# Topshell_V1_2.net
KiCad netlist of a schematic drawn in EAGLE
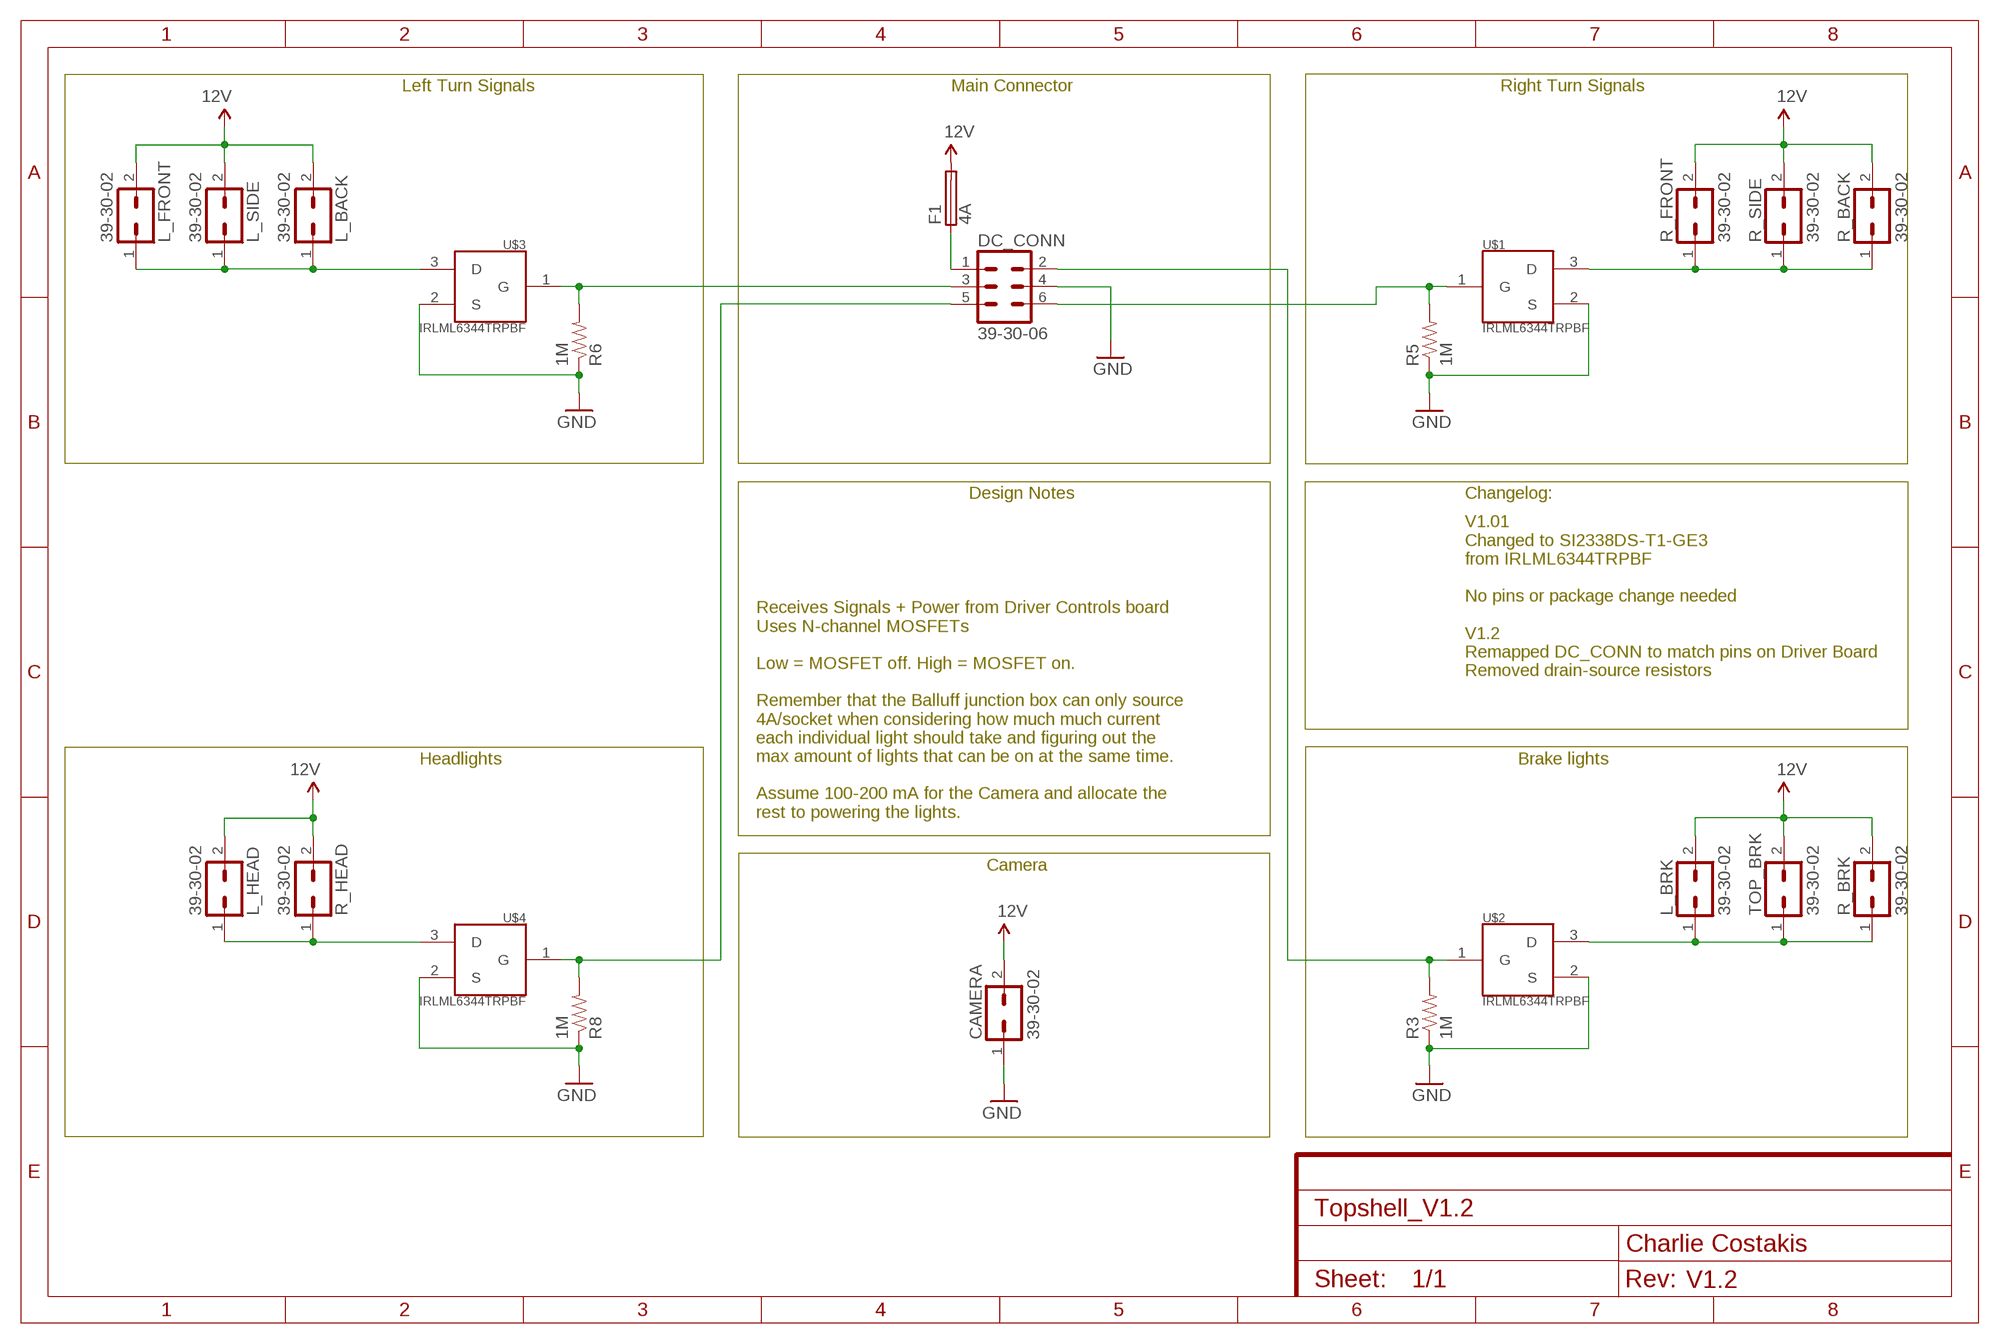
[diagram p0: schematic, sheet 1]

(export (version "E")
  (design (tool "Eeschema 10.0.6"))
  (components
    (comp (ref "CAMERA")
      (value "39-30-02")
      (footprint "eagle-import:39-30-_02_")
      (libsource (lib "eagle-import") (part "39-30-?02?"))
    )
    (comp (ref "DC_CONN")
      (value "39-30-06")
      (footprint "eagle-import:39-30-_06_")
      (libsource (lib "eagle-import") (part "39-30-?06?"))
    )
    (comp (ref "F1")
      (value "4A")
      (footprint "eagle-import:OMNIBLOK")
      (libsource (lib "eagle-import") (part "SMD-MICRO-FUSE-BLOCK"))
    )
    (comp (ref "L_BACK")
      (value "39-30-02")
      (footprint "eagle-import:39-30-_02_")
      (libsource (lib "eagle-import") (part "39-30-?02?"))
    )
    (comp (ref "L_BRK")
      (value "39-30-02")
      (footprint "eagle-import:39-30-_02_")
      (libsource (lib "eagle-import") (part "39-30-?02?"))
    )
    (comp (ref "L_FRONT")
      (value "39-30-02")
      (footprint "eagle-import:39-30-_02_")
      (libsource (lib "eagle-import") (part "39-30-?02?"))
    )
    (comp (ref "L_HEAD")
      (value "39-30-02")
      (footprint "eagle-import:39-30-_02_")
      (libsource (lib "eagle-import") (part "39-30-?02?"))
    )
    (comp (ref "L_SIDE")
      (value "39-30-02")
      (footprint "eagle-import:39-30-_02_")
      (libsource (lib "eagle-import") (part "39-30-?02?"))
    )
    (comp (ref "R3")
      (value "1M")
      (footprint "eagle-import:0805")
      (libsource (lib "eagle-import") (part "RESISTOR0805-RES"))
    )
    (comp (ref "R5")
      (value "1M")
      (footprint "eagle-import:0805")
      (libsource (lib "eagle-import") (part "RESISTOR0805-RES"))
    )
    (comp (ref "R6")
      (value "1M")
      (footprint "eagle-import:0805")
      (libsource (lib "eagle-import") (part "RESISTOR0805-RES"))
    )
    (comp (ref "R8")
      (value "1M")
      (footprint "eagle-import:0805")
      (libsource (lib "eagle-import") (part "RESISTOR0805-RES"))
    )
    (comp (ref "R_BACK")
      (value "39-30-02")
      (footprint "eagle-import:39-30-_02_")
      (libsource (lib "eagle-import") (part "39-30-?02?"))
    )
    (comp (ref "R_BRK")
      (value "39-30-02")
      (footprint "eagle-import:39-30-_02_")
      (libsource (lib "eagle-import") (part "39-30-?02?"))
    )
    (comp (ref "R_FRONT")
      (value "39-30-02")
      (footprint "eagle-import:39-30-_02_")
      (libsource (lib "eagle-import") (part "39-30-?02?"))
    )
    (comp (ref "R_HEAD")
      (value "39-30-02")
      (footprint "eagle-import:39-30-_02_")
      (libsource (lib "eagle-import") (part "39-30-?02?"))
    )
    (comp (ref "R_SIDE")
      (value "39-30-02")
      (footprint "eagle-import:39-30-_02_")
      (libsource (lib "eagle-import") (part "39-30-?02?"))
    )
    (comp (ref "TOP_BRK")
      (value "39-30-02")
      (footprint "eagle-import:39-30-_02_")
      (libsource (lib "eagle-import") (part "39-30-?02?"))
    )
    (comp (ref "U$1")
      (value "IRLML6344TRPBF")
      (footprint "eagle-import:SOT23")
      (libsource (lib "eagle-import") (part "IRLML6344TRPBF"))
    )
    (comp (ref "U$2")
      (value "IRLML6344TRPBF")
      (footprint "eagle-import:SOT23")
      (libsource (lib "eagle-import") (part "IRLML6344TRPBF"))
    )
    (comp (ref "U$3")
      (value "IRLML6344TRPBF")
      (footprint "eagle-import:SOT23")
      (libsource (lib "eagle-import") (part "IRLML6344TRPBF"))
    )
    (comp (ref "U$4")
      (value "IRLML6344TRPBF")
      (footprint "eagle-import:SOT23")
      (libsource (lib "eagle-import") (part "IRLML6344TRPBF"))
    )
  )
  (nets
    (net (code "1") (name "12V") (class "Default")
      (node (ref "CAMERA") (pin "2") (pinfunction "2_2") (pintype "passive"))
      (node (ref "F1") (pin "P$2") (pinfunction "2_P$2") (pintype "passive"))
      (node (ref "L_BACK") (pin "2") (pinfunction "2_2") (pintype "passive"))
      (node (ref "L_BRK") (pin "2") (pinfunction "2_2") (pintype "passive"))
      (node (ref "L_FRONT") (pin "2") (pinfunction "2_2") (pintype "passive"))
      (node (ref "L_HEAD") (pin "2") (pinfunction "2_2") (pintype "passive"))
      (node (ref "L_SIDE") (pin "2") (pinfunction "2_2") (pintype "passive"))
      (node (ref "R_BACK") (pin "2") (pinfunction "2_2") (pintype "passive"))
      (node (ref "R_BRK") (pin "2") (pinfunction "2_2") (pintype "passive"))
      (node (ref "R_FRONT") (pin "2") (pinfunction "2_2") (pintype "passive"))
      (node (ref "R_HEAD") (pin "2") (pinfunction "2_2") (pintype "passive"))
      (node (ref "R_SIDE") (pin "2") (pinfunction "2_2") (pintype "passive"))
      (node (ref "TOP_BRK") (pin "2") (pinfunction "2_2") (pintype "passive"))
    )
    (net (code "2") (name "GND") (class "Default")
      (node (ref "CAMERA") (pin "1") (pinfunction "1_1") (pintype "passive"))
      (node (ref "DC_CONN") (pin "4") (pinfunction "4_4") (pintype "passive"))
      (node (ref "R3") (pin "1") (pinfunction "1_1") (pintype "passive"))
      (node (ref "R5") (pin "1") (pinfunction "1_1") (pintype "passive"))
      (node (ref "R6") (pin "1") (pinfunction "1_1") (pintype "passive"))
      (node (ref "R8") (pin "1") (pinfunction "1_1") (pintype "passive"))
      (node (ref "U$1") (pin "2") (pinfunction "S_2") (pintype "bidirectional"))
      (node (ref "U$2") (pin "2") (pinfunction "S_2") (pintype "bidirectional"))
      (node (ref "U$3") (pin "2") (pinfunction "S_2") (pintype "bidirectional"))
      (node (ref "U$4") (pin "2") (pinfunction "S_2") (pintype "bidirectional"))
    )
    (net (code "3") (name "Net-(F1-1)") (class "Default")
      (node (ref "DC_CONN") (pin "1") (pinfunction "1_1") (pintype "passive"))
      (node (ref "F1") (pin "P$1") (pinfunction "1_P$1") (pintype "passive"))
    )
    (net (code "4") (name "Net-(U$1-D)") (class "Default")
      (node (ref "R_BACK") (pin "1") (pinfunction "1_1") (pintype "passive"))
      (node (ref "R_FRONT") (pin "1") (pinfunction "1_1") (pintype "passive"))
      (node (ref "R_SIDE") (pin "1") (pinfunction "1_1") (pintype "passive"))
      (node (ref "U$1") (pin "3") (pinfunction "D_3") (pintype "bidirectional"))
    )
    (net (code "5") (name "Net-(U$1-G)") (class "Default")
      (node (ref "DC_CONN") (pin "6") (pinfunction "6_6") (pintype "passive"))
      (node (ref "R5") (pin "2") (pinfunction "2_2") (pintype "passive"))
      (node (ref "U$1") (pin "1") (pinfunction "G_1") (pintype "bidirectional"))
    )
    (net (code "6") (name "Net-(U$2-D)") (class "Default")
      (node (ref "L_BRK") (pin "1") (pinfunction "1_1") (pintype "passive"))
      (node (ref "R_BRK") (pin "1") (pinfunction "1_1") (pintype "passive"))
      (node (ref "TOP_BRK") (pin "1") (pinfunction "1_1") (pintype "passive"))
      (node (ref "U$2") (pin "3") (pinfunction "D_3") (pintype "bidirectional"))
    )
    (net (code "7") (name "Net-(U$2-G)") (class "Default")
      (node (ref "DC_CONN") (pin "2") (pinfunction "2_2") (pintype "passive"))
      (node (ref "R3") (pin "2") (pinfunction "2_2") (pintype "passive"))
      (node (ref "U$2") (pin "1") (pinfunction "G_1") (pintype "bidirectional"))
    )
    (net (code "8") (name "Net-(U$3-D)") (class "Default")
      (node (ref "L_BACK") (pin "1") (pinfunction "1_1") (pintype "passive"))
      (node (ref "L_FRONT") (pin "1") (pinfunction "1_1") (pintype "passive"))
      (node (ref "L_SIDE") (pin "1") (pinfunction "1_1") (pintype "passive"))
      (node (ref "U$3") (pin "3") (pinfunction "D_3") (pintype "bidirectional"))
    )
    (net (code "9") (name "Net-(U$3-G)") (class "Default")
      (node (ref "DC_CONN") (pin "3") (pinfunction "3_3") (pintype "passive"))
      (node (ref "R6") (pin "2") (pinfunction "2_2") (pintype "passive"))
      (node (ref "U$3") (pin "1") (pinfunction "G_1") (pintype "bidirectional"))
    )
    (net (code "10") (name "Net-(U$4-D)") (class "Default")
      (node (ref "L_HEAD") (pin "1") (pinfunction "1_1") (pintype "passive"))
      (node (ref "R_HEAD") (pin "1") (pinfunction "1_1") (pintype "passive"))
      (node (ref "U$4") (pin "3") (pinfunction "D_3") (pintype "bidirectional"))
    )
    (net (code "11") (name "Net-(U$4-G)") (class "Default")
      (node (ref "DC_CONN") (pin "5") (pinfunction "5_5") (pintype "passive"))
      (node (ref "R8") (pin "2") (pinfunction "2_2") (pintype "passive"))
      (node (ref "U$4") (pin "1") (pinfunction "G_1") (pintype "bidirectional"))
    )
  )
)
